# yard-ice-fpga.net
KiCad netlist of a schematic drawn in Altium Designer
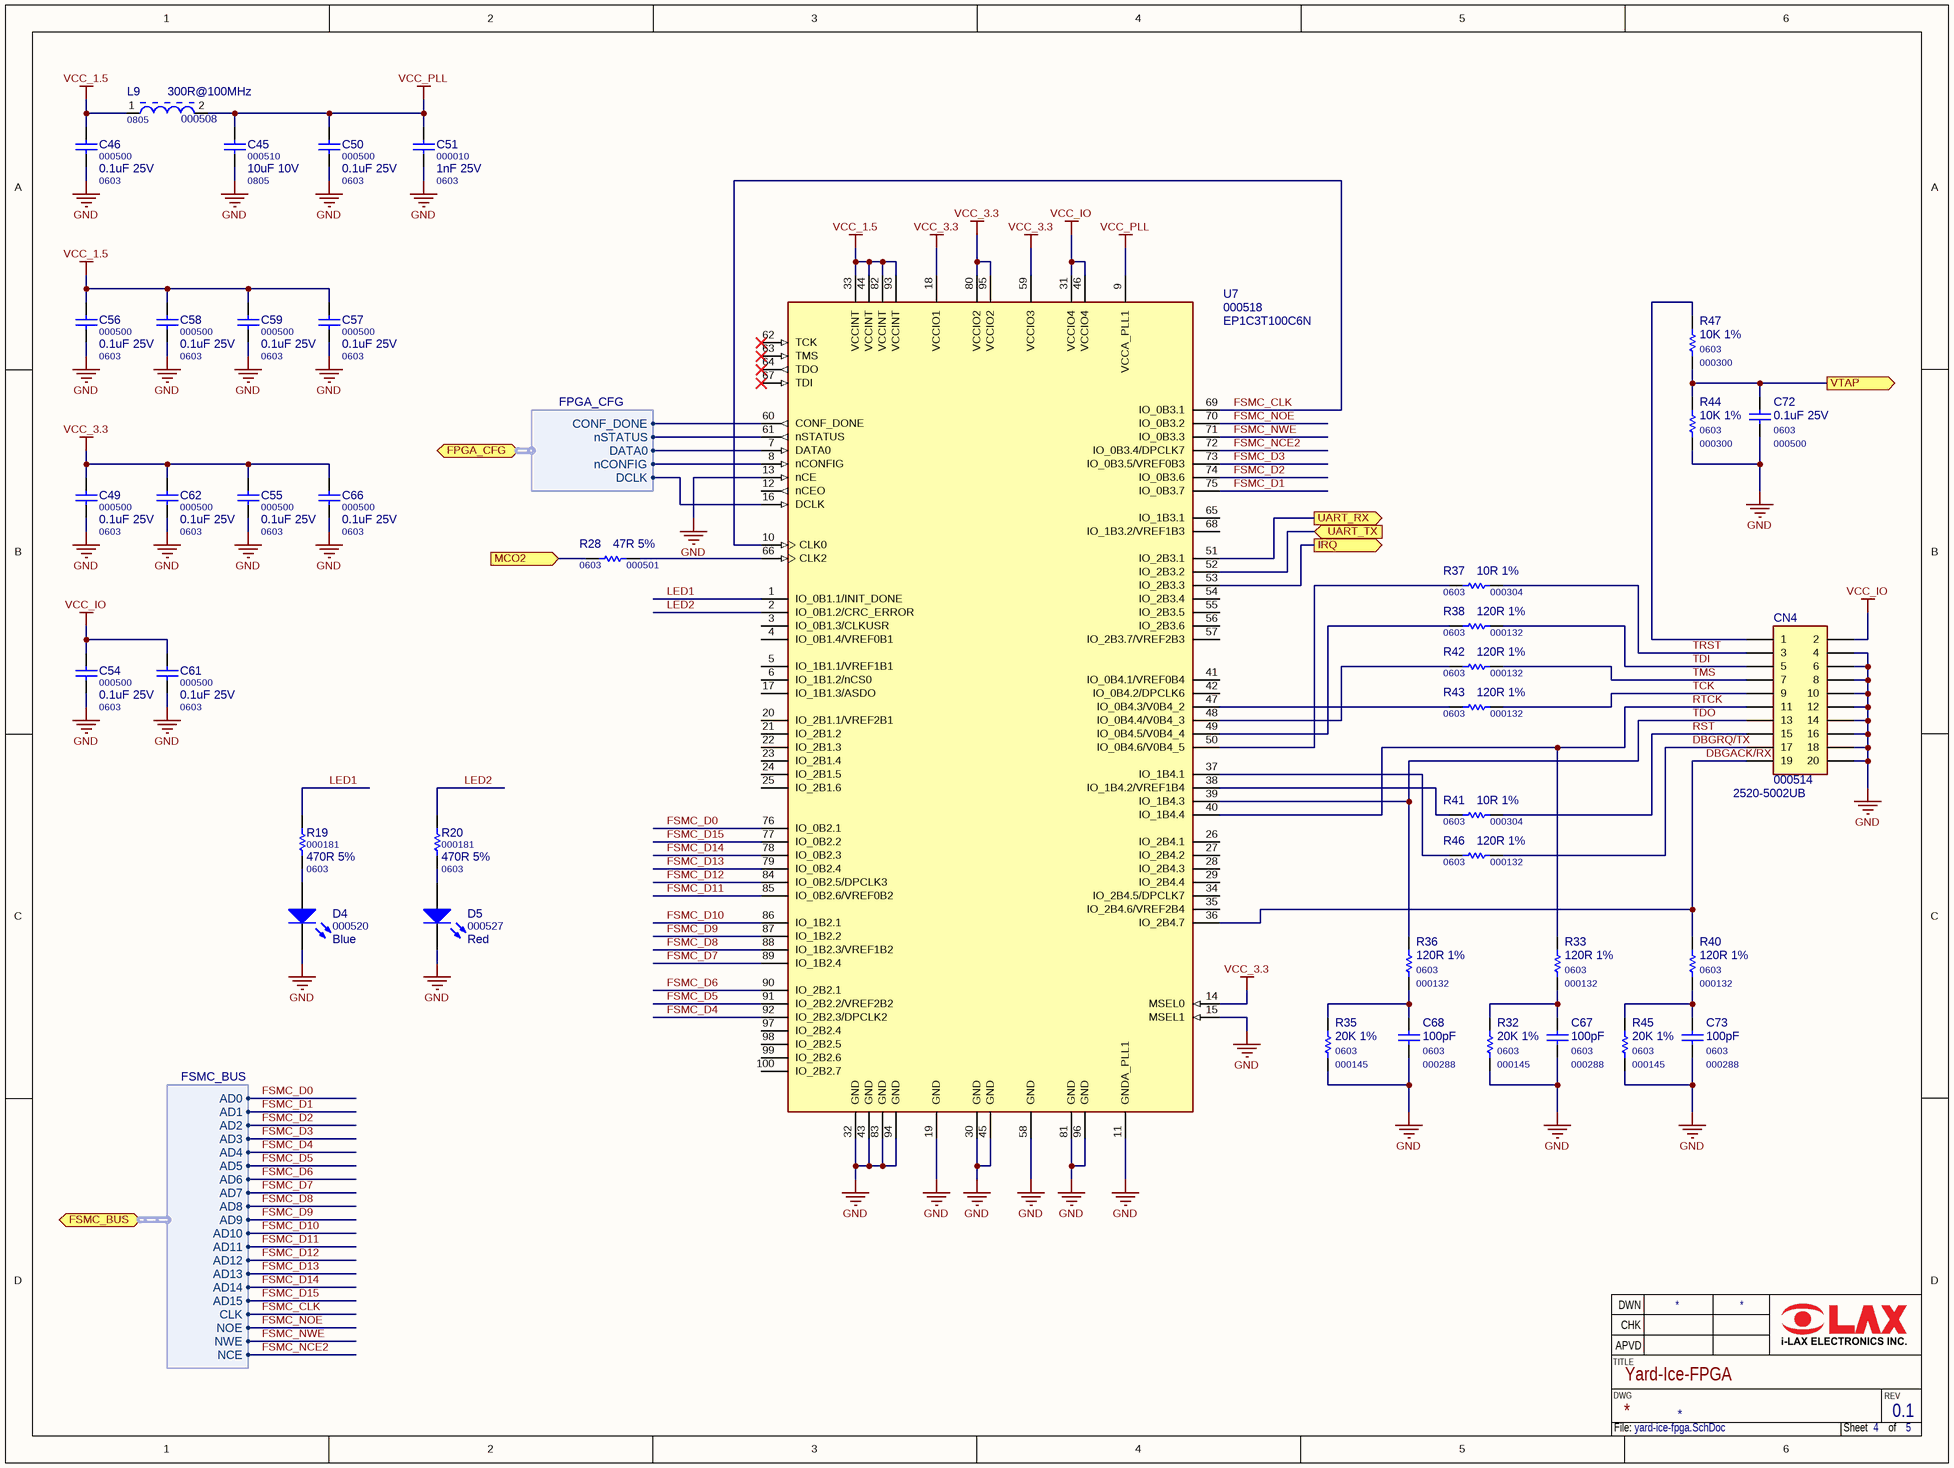
[diagram p0: yard-ice-fpga.SchDoc]

(export (version "E")
  (design (tool "Eeschema 10.0.6"))
  (components
    (comp (ref "C45")
      (value "000510")
      (footprint "C0805M")
      (description "SMD Ceramic Chip Capacitor - 0805 - X7R")
      (fields
        (field (name "ALTIUM_VALUE") "10uF 10V")
        (field (name "PACKAGE") "0805")
        (field (name "MF") "TDK")
      )
      (libsource (lib "discrete-sm") (part "C0805"))
    )
    (comp (ref "C46")
      (value "000500")
      (footprint "C0603M")
      (description "SMD Ceramic Chip Capacitor - 0603 - X7R")
      (fields
        (field (name "ALTIUM_VALUE") "0.1uF 25V")
        (field (name "PACKAGE") "0603")
        (field (name "MF") "TDK")
      )
      (libsource (lib "discrete-sm") (part "C0603"))
    )
    (comp (ref "C49")
      (value "000500")
      (footprint "C0603M")
      (description "SMD Ceramic Chip Capacitor - 0603 - X7R")
      (fields
        (field (name "ALTIUM_VALUE") "0.1uF 25V")
        (field (name "PACKAGE") "0603")
        (field (name "MF") "TDK")
      )
      (libsource (lib "discrete-sm") (part "C0603"))
    )
    (comp (ref "C50")
      (value "000500")
      (footprint "C0603M")
      (description "SMD Ceramic Chip Capacitor - 0603 - X7R")
      (fields
        (field (name "ALTIUM_VALUE") "0.1uF 25V")
        (field (name "PACKAGE") "0603")
        (field (name "MF") "TDK")
      )
      (libsource (lib "discrete-sm") (part "C0603"))
    )
    (comp (ref "C51")
      (value "000010")
      (footprint "C0603M")
      (description "SMD Ceramic Chip Capacitor - 0603 - X7R")
      (fields (field (name "ALTIUM_VALUE") "1nF 25V") (field (name "PACKAGE") "0603"))
      (libsource (lib "discrete-sm") (part "C0603"))
    )
    (comp (ref "C54")
      (value "000500")
      (footprint "C0603M")
      (description "SMD Ceramic Chip Capacitor - 0603 - X7R")
      (fields
        (field (name "ALTIUM_VALUE") "0.1uF 25V")
        (field (name "PACKAGE") "0603")
        (field (name "MF") "TDK")
      )
      (libsource (lib "discrete-sm") (part "C0603"))
    )
    (comp (ref "C55")
      (value "000500")
      (footprint "C0603M")
      (description "SMD Ceramic Chip Capacitor - 0603 - X7R")
      (fields
        (field (name "ALTIUM_VALUE") "0.1uF 25V")
        (field (name "PACKAGE") "0603")
        (field (name "MF") "TDK")
      )
      (libsource (lib "discrete-sm") (part "C0603"))
    )
    (comp (ref "C56")
      (value "000500")
      (footprint "C0603M")
      (description "SMD Ceramic Chip Capacitor - 0603 - X7R")
      (fields
        (field (name "ALTIUM_VALUE") "0.1uF 25V")
        (field (name "PACKAGE") "0603")
        (field (name "MF") "TDK")
      )
      (libsource (lib "discrete-sm") (part "C0603"))
    )
    (comp (ref "C57")
      (value "000500")
      (footprint "C0603M")
      (description "SMD Ceramic Chip Capacitor - 0603 - X7R")
      (fields
        (field (name "ALTIUM_VALUE") "0.1uF 25V")
        (field (name "PACKAGE") "0603")
        (field (name "MF") "TDK")
      )
      (libsource (lib "discrete-sm") (part "C0603"))
    )
    (comp (ref "C58")
      (value "000500")
      (footprint "C0603M")
      (description "SMD Ceramic Chip Capacitor - 0603 - X7R")
      (fields
        (field (name "ALTIUM_VALUE") "0.1uF 25V")
        (field (name "PACKAGE") "0603")
        (field (name "MF") "TDK")
      )
      (libsource (lib "discrete-sm") (part "C0603"))
    )
    (comp (ref "C59")
      (value "000500")
      (footprint "C0603M")
      (description "SMD Ceramic Chip Capacitor - 0603 - X7R")
      (fields
        (field (name "ALTIUM_VALUE") "0.1uF 25V")
        (field (name "PACKAGE") "0603")
        (field (name "MF") "TDK")
      )
      (libsource (lib "discrete-sm") (part "C0603"))
    )
    (comp (ref "C61")
      (value "000500")
      (footprint "C0603M")
      (description "SMD Ceramic Chip Capacitor - 0603 - X7R")
      (fields
        (field (name "ALTIUM_VALUE") "0.1uF 25V")
        (field (name "PACKAGE") "0603")
        (field (name "MF") "TDK")
      )
      (libsource (lib "discrete-sm") (part "C0603"))
    )
    (comp (ref "C62")
      (value "000500")
      (footprint "C0603M")
      (description "SMD Ceramic Chip Capacitor - 0603 - X7R")
      (fields
        (field (name "ALTIUM_VALUE") "0.1uF 25V")
        (field (name "PACKAGE") "0603")
        (field (name "MF") "TDK")
      )
      (libsource (lib "discrete-sm") (part "C0603"))
    )
    (comp (ref "C66")
      (value "000500")
      (footprint "C0603M")
      (description "SMD Ceramic Chip Capacitor - 0603 - X7R")
      (fields
        (field (name "ALTIUM_VALUE") "0.1uF 25V")
        (field (name "PACKAGE") "0603")
        (field (name "MF") "TDK")
      )
      (libsource (lib "discrete-sm") (part "C0603"))
    )
    (comp (ref "C67")
      (value "000288")
      (footprint "C0603M")
      (description "SMD Ceramic Chip Capacitor - 0603")
      (fields (field (name "ALTIUM_VALUE") "100pF") (field (name "PACKAGE") "0603"))
      (libsource (lib "discrete-sm") (part "C0603"))
    )
    (comp (ref "C68")
      (value "000288")
      (footprint "C0603M")
      (description "SMD Ceramic Chip Capacitor - 0603")
      (fields (field (name "ALTIUM_VALUE") "100pF") (field (name "PACKAGE") "0603"))
      (libsource (lib "discrete-sm") (part "C0603"))
    )
    (comp (ref "C72")
      (value "000500")
      (footprint "C0603M")
      (description "SMD Ceramic Chip Capacitor - 0603 - X7R")
      (fields
        (field (name "ALTIUM_VALUE") "0.1uF 25V")
        (field (name "PACKAGE") "0603")
        (field (name "MF") "TDK")
      )
      (libsource (lib "discrete-sm") (part "C0603"))
    )
    (comp (ref "C73")
      (value "000288")
      (footprint "C0603M")
      (description "SMD Ceramic Chip Capacitor - 0603")
      (fields (field (name "ALTIUM_VALUE") "100pF") (field (name "PACKAGE") "0603"))
      (libsource (lib "discrete-sm") (part "C0603"))
    )
    (comp (ref "CN4")
      (value "000514")
      (footprint "TST-110-04-G-D-RA")
      (description "Shrouded Header, 20 Pos, Right Angle")
      (fields (field (name "ALTIUM_VALUE") "2520-5002UB") (field (name "MF") "3M"))
      (libsource (lib "samtec-board-to-board") (part "Header 10X2"))
    )
    (comp (ref "D4")
      (value "000520")
      (footprint "LED0805L LP")
      (description "LED SMD 0805")
      (fields (field (name "ALTIUM_VALUE") "Blue"))
      (libsource (lib "discrete-sm") (part "LED0805LP"))
    )
    (comp (ref "D5")
      (value "000527")
      (footprint "LED0805L LP")
      (description "LED SMD 0805")
      (fields (field (name "ALTIUM_VALUE") "Red"))
      (libsource (lib "discrete-sm") (part "LED0805LP"))
    )
    (comp (ref "L9")
      (value "000508")
      (footprint "L0805M")
      (description "SMD Ferrite Bead 0805")
      (fields
        (field (name "ALTIUM_VALUE") "300R@100MHz")
        (field (name "PACKAGE") "0805")
        (field (name "MF") "TDK")
      )
      (libsource (lib "discrete-sm") (part "L0805"))
    )
    (comp (ref "R19")
      (value "000181")
      (footprint "R0603M")
      (description "SMD Chip Resistor - 0603")
      (fields (field (name "ALTIUM_VALUE") "470R 5%") (field (name "PACKAGE") "0603"))
      (libsource (lib "discrete-sm") (part "R0603"))
    )
    (comp (ref "R20")
      (value "000181")
      (footprint "R0603M")
      (description "SMD Chip Resistor - 0603")
      (fields (field (name "ALTIUM_VALUE") "470R 5%") (field (name "PACKAGE") "0603"))
      (libsource (lib "discrete-sm") (part "R0603"))
    )
    (comp (ref "R28")
      (value "000501")
      (footprint "R0603M")
      (description "SMD Chip Resistor - 0603")
      (fields (field (name "ALTIUM_VALUE") "47R 5%") (field (name "PACKAGE") "0603"))
      (libsource (lib "discrete-sm") (part "R0603"))
    )
    (comp (ref "R32")
      (value "000145")
      (footprint "R0603M")
      (description "SMD Chip Resistor - 0603")
      (fields (field (name "ALTIUM_VALUE") "20K 1%") (field (name "PACKAGE") "0603"))
      (libsource (lib "discrete-sm") (part "R0603"))
    )
    (comp (ref "R33")
      (value "000132")
      (footprint "R0603M")
      (description "SMD Chip Resistor - 0603")
      (fields (field (name "ALTIUM_VALUE") "120R 1%") (field (name "PACKAGE") "0603"))
      (libsource (lib "discrete-sm") (part "R0603"))
    )
    (comp (ref "R35")
      (value "000145")
      (footprint "R0603M")
      (description "SMD Chip Resistor - 0603")
      (fields (field (name "ALTIUM_VALUE") "20K 1%") (field (name "PACKAGE") "0603"))
      (libsource (lib "discrete-sm") (part "R0603"))
    )
    (comp (ref "R36")
      (value "000132")
      (footprint "R0603M")
      (description "SMD Chip Resistor - 0603")
      (fields (field (name "ALTIUM_VALUE") "120R 1%") (field (name "PACKAGE") "0603"))
      (libsource (lib "discrete-sm") (part "R0603"))
    )
    (comp (ref "R37")
      (value "000304")
      (footprint "R0603M")
      (description "SMD Chip Resistor - 0603")
      (fields (field (name "ALTIUM_VALUE") "10R 1%") (field (name "PACKAGE") "0603"))
      (libsource (lib "discrete-sm") (part "R0603"))
    )
    (comp (ref "R38")
      (value "000132")
      (footprint "R0603M")
      (description "SMD Chip Resistor - 0603")
      (fields (field (name "ALTIUM_VALUE") "120R 1%") (field (name "PACKAGE") "0603"))
      (libsource (lib "discrete-sm") (part "R0603"))
    )
    (comp (ref "R40")
      (value "000132")
      (footprint "R0603M")
      (description "SMD Chip Resistor - 0603")
      (fields (field (name "ALTIUM_VALUE") "120R 1%") (field (name "PACKAGE") "0603"))
      (libsource (lib "discrete-sm") (part "R0603"))
    )
    (comp (ref "R41")
      (value "000304")
      (footprint "R0603M")
      (description "SMD Chip Resistor - 0603")
      (fields (field (name "ALTIUM_VALUE") "10R 1%") (field (name "PACKAGE") "0603"))
      (libsource (lib "discrete-sm") (part "R0603"))
    )
    (comp (ref "R42")
      (value "000132")
      (footprint "R0603M")
      (description "SMD Chip Resistor - 0603")
      (fields (field (name "ALTIUM_VALUE") "120R 1%") (field (name "PACKAGE") "0603"))
      (libsource (lib "discrete-sm") (part "R0603"))
    )
    (comp (ref "R43")
      (value "000132")
      (footprint "R0603M")
      (description "SMD Chip Resistor - 0603")
      (fields (field (name "ALTIUM_VALUE") "120R 1%") (field (name "PACKAGE") "0603"))
      (libsource (lib "discrete-sm") (part "R0603"))
    )
    (comp (ref "R44")
      (value "000300")
      (footprint "R0603M")
      (description "SMD Chip Resistor - 0603")
      (fields (field (name "ALTIUM_VALUE") "10K 1%") (field (name "PACKAGE") "0603"))
      (libsource (lib "discrete-sm") (part "R0603"))
    )
    (comp (ref "R45")
      (value "000145")
      (footprint "R0603M")
      (description "SMD Chip Resistor - 0603")
      (fields (field (name "ALTIUM_VALUE") "20K 1%") (field (name "PACKAGE") "0603"))
      (libsource (lib "discrete-sm") (part "R0603"))
    )
    (comp (ref "R46")
      (value "000132")
      (footprint "R0603M")
      (description "SMD Chip Resistor - 0603")
      (fields (field (name "ALTIUM_VALUE") "120R 1%") (field (name "PACKAGE") "0603"))
      (libsource (lib "discrete-sm") (part "R0603"))
    )
    (comp (ref "R47")
      (value "000300")
      (footprint "R0603M")
      (description "SMD Chip Resistor - 0603")
      (fields (field (name "ALTIUM_VALUE") "10K 1%") (field (name "PACKAGE") "0603"))
      (libsource (lib "discrete-sm") (part "R0603"))
    )
    (comp (ref "U7")
      (value "000518")
      (footprint "TQFP-100")
      (description "Cyclone FPGA")
      (fields (field (name "ALTIUM_VALUE") "EP1C3T100C6N") (field (name "MF") "Altera"))
      (libsource (lib "altera-cyclone") (part "EP1C3T100C8N"))
    )
  )
  (nets
    (net (code "3") (name "/CONF_DONE") (class "Default")
      (node (ref "U7") (pin "60") (pinfunction "CONF_DONE_60") (pintype "output"))
    )
    (net (code "4") (name "/DATA0") (class "Default")
      (node (ref "U7") (pin "7") (pinfunction "DATA0_7") (pintype "input"))
    )
    (net (code "5") (name "/DBGACK{slash}RX") (class "Default")
      (node (ref "CN4") (pin "19") (pinfunction "19_19") (pintype "passive"))
      (node (ref "R40") (pin "1") (pinfunction "1_1") (pintype "passive"))
      (node (ref "U7") (pin "36") (pinfunction "IO_2B4.7_36") (pintype "tri_state"))
    )
    (net (code "6") (name "/DBGRQ{slash}TX") (class "Default")
      (node (ref "CN4") (pin "17") (pinfunction "17_17") (pintype "passive"))
      (node (ref "R46") (pin "1") (pinfunction "1_1") (pintype "passive"))
    )
    (net (code "7") (name "/DCLK") (class "Default")
      (node (ref "U7") (pin "16") (pinfunction "DCLK_16") (pintype "input"))
    )
    (net (code "8") (name "/FSMC_CLK") (class "Default")
      (node (ref "U7") (pin "10") (pinfunction "CLK0_10") (pintype "input"))
      (node (ref "U7") (pin "69") (pinfunction "IO_0B3.1_69") (pintype "tri_state"))
    )
    (net (code "9") (name "/FSMC_D0") (class "Default")
      (node (ref "U7") (pin "76") (pinfunction "IO_0B2.1_76") (pintype "tri_state"))
    )
    (net (code "10") (name "/FSMC_D1") (class "Default")
      (node (ref "U7") (pin "75") (pinfunction "IO_0B3.7_75") (pintype "tri_state"))
    )
    (net (code "11") (name "/FSMC_D2") (class "Default")
      (node (ref "U7") (pin "74") (pinfunction "IO_0B3.6_74") (pintype "tri_state"))
    )
    (net (code "12") (name "/FSMC_D3") (class "Default")
      (node (ref "U7") (pin "73") (pinfunction "IO_0B3.5/VREF0B3_73") (pintype "tri_state"))
    )
    (net (code "13") (name "/FSMC_D4") (class "Default")
      (node (ref "U7") (pin "92") (pinfunction "IO_2B2.3/DPCLK2_92") (pintype "tri_state"))
    )
    (net (code "14") (name "/FSMC_D5") (class "Default")
      (node (ref "U7") (pin "91") (pinfunction "IO_2B2.2/VREF2B2_91") (pintype "tri_state"))
    )
    (net (code "15") (name "/FSMC_D6") (class "Default")
      (node (ref "U7") (pin "90") (pinfunction "IO_2B2.1_90") (pintype "tri_state"))
    )
    (net (code "16") (name "/FSMC_D7") (class "Default")
      (node (ref "U7") (pin "89") (pinfunction "IO_1B2.4_89") (pintype "tri_state"))
    )
    (net (code "17") (name "/FSMC_D8") (class "Default")
      (node (ref "U7") (pin "88") (pinfunction "IO_1B2.3/VREF1B2_88") (pintype "tri_state"))
    )
    (net (code "18") (name "/FSMC_D9") (class "Default")
      (node (ref "U7") (pin "87") (pinfunction "IO_1B2.2_87") (pintype "tri_state"))
    )
    (net (code "19") (name "/FSMC_D10") (class "Default")
      (node (ref "U7") (pin "86") (pinfunction "IO_1B2.1_86") (pintype "tri_state"))
    )
    (net (code "20") (name "/FSMC_D11") (class "Default")
      (node (ref "U7") (pin "85") (pinfunction "IO_0B2.6/VREF0B2_85") (pintype "tri_state"))
    )
    (net (code "21") (name "/FSMC_D12") (class "Default")
      (node (ref "U7") (pin "84") (pinfunction "IO_0B2.5/DPCLK3_84") (pintype "tri_state"))
    )
    (net (code "22") (name "/FSMC_D13") (class "Default")
      (node (ref "U7") (pin "79") (pinfunction "IO_0B2.4_79") (pintype "tri_state"))
    )
    (net (code "23") (name "/FSMC_D14") (class "Default")
      (node (ref "U7") (pin "78") (pinfunction "IO_0B2.3_78") (pintype "tri_state"))
    )
    (net (code "24") (name "/FSMC_D15") (class "Default")
      (node (ref "U7") (pin "77") (pinfunction "IO_0B2.2_77") (pintype "tri_state"))
    )
    (net (code "25") (name "/FSMC_NCE2") (class "Default")
      (node (ref "U7") (pin "72") (pinfunction "IO_0B3.4/DPCLK7_72") (pintype "tri_state"))
    )
    (net (code "26") (name "/FSMC_NOE") (class "Default")
      (node (ref "U7") (pin "70") (pinfunction "IO_0B3.2_70") (pintype "tri_state"))
    )
    (net (code "27") (name "/FSMC_NWE") (class "Default")
      (node (ref "U7") (pin "71") (pinfunction "IO_0B3.3_71") (pintype "tri_state"))
    )
    (net (code "28") (name "/IRQ") (class "Default")
      (node (ref "U7") (pin "53") (pinfunction "IO_2B3.3_53") (pintype "tri_state"))
    )
    (net (code "29") (name "/LED1") (class "Default")
      (node (ref "R19") (pin "1") (pinfunction "1_1") (pintype "passive"))
      (node (ref "U7") (pin "1") (pinfunction "IO_0B1.1/INIT_DONE_1") (pintype "tri_state"))
    )
    (net (code "30") (name "/LED2") (class "Default")
      (node (ref "R20") (pin "1") (pinfunction "1_1") (pintype "passive"))
      (node (ref "U7") (pin "2") (pinfunction "IO_0B1.2/CRC_ERROR_2") (pintype "tri_state"))
    )
    (net (code "31") (name "/MCO2") (class "Default")
      (node (ref "R28") (pin "2") (pinfunction "2_2") (pintype "passive"))
    )
    (net (code "32") (name "/RST") (class "Default")
      (node (ref "CN4") (pin "15") (pinfunction "15_15") (pintype "passive"))
      (node (ref "R41") (pin "1") (pinfunction "1_1") (pintype "passive"))
    )
    (net (code "33") (name "/RTCK") (class "Default")
      (node (ref "CN4") (pin "11") (pinfunction "11_11") (pintype "passive"))
      (node (ref "R33") (pin "1") (pinfunction "1_1") (pintype "passive"))
      (node (ref "U7") (pin "40") (pinfunction "IO_1B4.4_40") (pintype "tri_state"))
    )
    (net (code "34") (name "/TCK") (class "Default")
      (node (ref "CN4") (pin "9") (pinfunction "9_9") (pintype "passive"))
      (node (ref "R43") (pin "1") (pinfunction "1_1") (pintype "passive"))
    )
    (net (code "35") (name "/TDI") (class "Default")
      (node (ref "CN4") (pin "5") (pinfunction "5_5") (pintype "passive"))
      (node (ref "R38") (pin "1") (pinfunction "1_1") (pintype "passive"))
    )
    (net (code "36") (name "/TDO") (class "Default")
      (node (ref "CN4") (pin "13") (pinfunction "13_13") (pintype "passive"))
      (node (ref "R36") (pin "1") (pinfunction "1_1") (pintype "passive"))
      (node (ref "U7") (pin "39") (pinfunction "IO_1B4.3_39") (pintype "tri_state"))
    )
    (net (code "37") (name "/TMS") (class "Default")
      (node (ref "CN4") (pin "7") (pinfunction "7_7") (pintype "passive"))
      (node (ref "R42") (pin "1") (pinfunction "1_1") (pintype "passive"))
    )
    (net (code "38") (name "/TRST") (class "Default")
      (node (ref "CN4") (pin "3") (pinfunction "3_3") (pintype "passive"))
      (node (ref "R37") (pin "1") (pinfunction "1_1") (pintype "passive"))
    )
    (net (code "39") (name "/UART_RX") (class "Default")
      (node (ref "U7") (pin "51") (pinfunction "IO_2B3.1_51") (pintype "tri_state"))
    )
    (net (code "40") (name "/UART_TX") (class "Default")
      (node (ref "U7") (pin "52") (pinfunction "IO_2B3.2_52") (pintype "tri_state"))
    )
    (net (code "41") (name "/VTAP") (class "Default")
      (node (ref "C72") (pin "1") (pinfunction "1_1") (pintype "passive"))
      (node (ref "R44") (pin "1") (pinfunction "1_1") (pintype "passive"))
      (node (ref "R47") (pin "2") (pinfunction "2_2") (pintype "passive"))
    )
    (net (code "42") (name "/nCONFIG") (class "Default")
      (node (ref "U7") (pin "8") (pinfunction "nCONFIG_8") (pintype "input"))
    )
    (net (code "43") (name "/nSTATUS") (class "Default")
      (node (ref "U7") (pin "61") (pinfunction "nSTATUS_61") (pintype "output"))
    )
    (net (code "46") (name "GND") (class "Default")
      (node (ref "C45") (pin "2") (pinfunction "2_2") (pintype "passive"))
      (node (ref "C46") (pin "2") (pinfunction "2_2") (pintype "passive"))
      (node (ref "C49") (pin "2") (pinfunction "2_2") (pintype "passive"))
      (node (ref "C50") (pin "2") (pinfunction "2_2") (pintype "passive"))
      (node (ref "C51") (pin "2") (pinfunction "2_2") (pintype "passive"))
      (node (ref "C54") (pin "2") (pinfunction "2_2") (pintype "passive"))
      (node (ref "C55") (pin "2") (pinfunction "2_2") (pintype "passive"))
      (node (ref "C56") (pin "2") (pinfunction "2_2") (pintype "passive"))
      (node (ref "C57") (pin "2") (pinfunction "2_2") (pintype "passive"))
      (node (ref "C58") (pin "2") (pinfunction "2_2") (pintype "passive"))
      (node (ref "C59") (pin "2") (pinfunction "2_2") (pintype "passive"))
      (node (ref "C61") (pin "2") (pinfunction "2_2") (pintype "passive"))
      (node (ref "C62") (pin "2") (pinfunction "2_2") (pintype "passive"))
      (node (ref "C66") (pin "2") (pinfunction "2_2") (pintype "passive"))
      (node (ref "C67") (pin "2") (pinfunction "2_2") (pintype "passive"))
      (node (ref "C68") (pin "2") (pinfunction "2_2") (pintype "passive"))
      (node (ref "C72") (pin "2") (pinfunction "2_2") (pintype "passive"))
      (node (ref "C73") (pin "2") (pinfunction "2_2") (pintype "passive"))
      (node (ref "CN4") (pin "10") (pinfunction "10_10") (pintype "passive"))
      (node (ref "CN4") (pin "12") (pinfunction "12_12") (pintype "passive"))
      (node (ref "CN4") (pin "14") (pinfunction "14_14") (pintype "passive"))
      (node (ref "CN4") (pin "16") (pinfunction "16_16") (pintype "passive"))
      (node (ref "CN4") (pin "18") (pinfunction "18_18") (pintype "passive"))
      (node (ref "CN4") (pin "20") (pinfunction "20_20") (pintype "passive"))
      (node (ref "CN4") (pin "4") (pinfunction "4_4") (pintype "passive"))
      (node (ref "CN4") (pin "6") (pinfunction "6_6") (pintype "passive"))
      (node (ref "CN4") (pin "8") (pinfunction "8_8") (pintype "passive"))
      (node (ref "D4") (pin "2") (pinfunction "K_2") (pintype "passive"))
      (node (ref "D5") (pin "2") (pinfunction "K_2") (pintype "passive"))
      (node (ref "R32") (pin "2") (pinfunction "2_2") (pintype "passive"))
      (node (ref "R35") (pin "2") (pinfunction "2_2") (pintype "passive"))
      (node (ref "R44") (pin "2") (pinfunction "2_2") (pintype "passive"))
      (node (ref "R45") (pin "2") (pinfunction "2_2") (pintype "passive"))
      (node (ref "U7") (pin "11") (pinfunction "GNDA_PLL1_11") (pintype "power_in"))
      (node (ref "U7") (pin "13") (pinfunction "nCE_13") (pintype "input"))
      (node (ref "U7") (pin "15") (pinfunction "MSEL1_15") (pintype "input"))
      (node (ref "U7") (pin "19") (pinfunction "GND_19") (pintype "power_in"))
      (node (ref "U7") (pin "30") (pinfunction "GND_30") (pintype "power_in"))
      (node (ref "U7") (pin "32") (pinfunction "GND_32") (pintype "power_in"))
      (node (ref "U7") (pin "43") (pinfunction "GND_43") (pintype "power_in"))
      (node (ref "U7") (pin "45") (pinfunction "GND_45") (pintype "power_in"))
      (node (ref "U7") (pin "58") (pinfunction "GND_58") (pintype "power_in"))
      (node (ref "U7") (pin "81") (pinfunction "GND_81") (pintype "power_in"))
      (node (ref "U7") (pin "83") (pinfunction "GND_83") (pintype "power_in"))
      (node (ref "U7") (pin "94") (pinfunction "GND_94") (pintype "power_in"))
      (node (ref "U7") (pin "96") (pinfunction "GND_96") (pintype "power_in"))
    )
    (net (code "47") (name "Net-(C67-Pad1)") (class "Default")
      (node (ref "C67") (pin "1") (pinfunction "1_1") (pintype "passive"))
      (node (ref "R32") (pin "1") (pinfunction "1_1") (pintype "passive"))
      (node (ref "R33") (pin "2") (pinfunction "2_2") (pintype "passive"))
    )
    (net (code "48") (name "Net-(C68-Pad1)") (class "Default")
      (node (ref "C68") (pin "1") (pinfunction "1_1") (pintype "passive"))
      (node (ref "R35") (pin "1") (pinfunction "1_1") (pintype "passive"))
      (node (ref "R36") (pin "2") (pinfunction "2_2") (pintype "passive"))
    )
    (net (code "49") (name "Net-(C73-Pad1)") (class "Default")
      (node (ref "C73") (pin "1") (pinfunction "1_1") (pintype "passive"))
      (node (ref "R40") (pin "2") (pinfunction "2_2") (pintype "passive"))
      (node (ref "R45") (pin "1") (pinfunction "1_1") (pintype "passive"))
    )
    (net (code "50") (name "Net-(CN4-Pad1)") (class "Default")
      (node (ref "CN4") (pin "1") (pinfunction "1_1") (pintype "passive"))
      (node (ref "R47") (pin "1") (pinfunction "1_1") (pintype "passive"))
    )
    (net (code "51") (name "Net-(D4-A)") (class "Default")
      (node (ref "D4") (pin "1") (pinfunction "A_1") (pintype "passive"))
      (node (ref "R19") (pin "2") (pinfunction "2_2") (pintype "passive"))
    )
    (net (code "52") (name "Net-(D5-A)") (class "Default")
      (node (ref "D5") (pin "1") (pinfunction "A_1") (pintype "passive"))
      (node (ref "R20") (pin "2") (pinfunction "2_2") (pintype "passive"))
    )
    (net (code "53") (name "Net-(U7-CLK2)") (class "Default")
      (node (ref "R28") (pin "1") (pinfunction "1_1") (pintype "passive"))
      (node (ref "U7") (pin "66") (pinfunction "CLK2_66") (pintype "input"))
    )
    (net (code "54") (name "Net-(U7-IO_0B4.3{slash}V0B4_2)") (class "Default")
      (node (ref "R43") (pin "2") (pinfunction "2_2") (pintype "passive"))
      (node (ref "U7") (pin "47") (pinfunction "IO_0B4.3/V0B4_2_47") (pintype "tri_state"))
    )
    (net (code "55") (name "Net-(U7-IO_0B4.4{slash}V0B4_3)") (class "Default")
      (node (ref "R42") (pin "2") (pinfunction "2_2") (pintype "passive"))
      (node (ref "U7") (pin "48") (pinfunction "IO_0B4.4/V0B4_3_48") (pintype "tri_state"))
    )
    (net (code "56") (name "Net-(U7-IO_0B4.5{slash}V0B4_4)") (class "Default")
      (node (ref "R38") (pin "2") (pinfunction "2_2") (pintype "passive"))
      (node (ref "U7") (pin "49") (pinfunction "IO_0B4.5/V0B4_4_49") (pintype "tri_state"))
    )
    (net (code "57") (name "Net-(U7-IO_0B4.6{slash}V0B4_5)") (class "Default")
      (node (ref "R37") (pin "2") (pinfunction "2_2") (pintype "passive"))
      (node (ref "U7") (pin "50") (pinfunction "IO_0B4.6/V0B4_5_50") (pintype "tri_state"))
    )
    (net (code "58") (name "Net-(U7-IO_1B4.1)") (class "Default")
      (node (ref "R46") (pin "2") (pinfunction "2_2") (pintype "passive"))
      (node (ref "U7") (pin "37") (pinfunction "IO_1B4.1_37") (pintype "tri_state"))
    )
    (net (code "59") (name "Net-(U7-IO_1B4.2{slash}VREF1B4)") (class "Default")
      (node (ref "R41") (pin "2") (pinfunction "2_2") (pintype "passive"))
      (node (ref "U7") (pin "38") (pinfunction "IO_1B4.2/VREF1B4_38") (pintype "tri_state"))
    )
    (net (code "60") (name "VCC_1.5") (class "Default")
      (node (ref "C46") (pin "1") (pinfunction "1_1") (pintype "passive"))
      (node (ref "C56") (pin "1") (pinfunction "1_1") (pintype "passive"))
      (node (ref "C57") (pin "1") (pinfunction "1_1") (pintype "passive"))
      (node (ref "C58") (pin "1") (pinfunction "1_1") (pintype "passive"))
      (node (ref "C59") (pin "1") (pinfunction "1_1") (pintype "passive"))
      (node (ref "L9") (pin "1") (pinfunction "1_1") (pintype "passive"))
      (node (ref "U7") (pin "33") (pinfunction "VCCINT_33") (pintype "power_in"))
      (node (ref "U7") (pin "44") (pinfunction "VCCINT_44") (pintype "power_in"))
      (node (ref "U7") (pin "82") (pinfunction "VCCINT_82") (pintype "power_in"))
      (node (ref "U7") (pin "93") (pinfunction "VCCINT_93") (pintype "power_in"))
    )
    (net (code "61") (name "VCC_3.3") (class "Default")
      (node (ref "C49") (pin "1") (pinfunction "1_1") (pintype "passive"))
      (node (ref "C55") (pin "1") (pinfunction "1_1") (pintype "passive"))
      (node (ref "C62") (pin "1") (pinfunction "1_1") (pintype "passive"))
      (node (ref "C66") (pin "1") (pinfunction "1_1") (pintype "passive"))
      (node (ref "U7") (pin "14") (pinfunction "MSEL0_14") (pintype "input"))
      (node (ref "U7") (pin "18") (pinfunction "VCCIO1_18") (pintype "power_in"))
      (node (ref "U7") (pin "59") (pinfunction "VCCIO3_59") (pintype "power_in"))
      (node (ref "U7") (pin "80") (pinfunction "VCCIO2_80") (pintype "power_in"))
      (node (ref "U7") (pin "95") (pinfunction "VCCIO2_95") (pintype "power_in"))
    )
    (net (code "62") (name "VCC_IO") (class "Default")
      (node (ref "C54") (pin "1") (pinfunction "1_1") (pintype "passive"))
      (node (ref "C61") (pin "1") (pinfunction "1_1") (pintype "passive"))
      (node (ref "CN4") (pin "2") (pinfunction "2_2") (pintype "passive"))
      (node (ref "U7") (pin "31") (pinfunction "VCCIO4_31") (pintype "power_in"))
      (node (ref "U7") (pin "46") (pinfunction "VCCIO4_46") (pintype "power_in"))
    )
    (net (code "63") (name "VCC_PLL") (class "Default")
      (node (ref "C45") (pin "1") (pinfunction "1_1") (pintype "passive"))
      (node (ref "C50") (pin "1") (pinfunction "1_1") (pintype "passive"))
      (node (ref "C51") (pin "1") (pinfunction "1_1") (pintype "passive"))
      (node (ref "L9") (pin "2") (pinfunction "2_2") (pintype "passive"))
      (node (ref "U7") (pin "9") (pinfunction "VCCA_PLL1_9") (pintype "power_in"))
    )
    (net (code "64") (name "unconnected-(U7-IO_0B1.3{slash}CLKUSR-Pad3)") (class "Default")
      (node (ref "U7") (pin "3") (pinfunction "IO_0B1.3/CLKUSR_3") (pintype "tri_state"))
    )
    (net (code "65") (name "unconnected-(U7-IO_0B1.4{slash}VREF0B1-Pad4)") (class "Default")
      (node (ref "U7") (pin "4") (pinfunction "IO_0B1.4/VREF0B1_4") (pintype "tri_state"))
    )
    (net (code "66") (name "unconnected-(U7-IO_0B4.1{slash}VREF0B4-Pad41)") (class "Default")
      (node (ref "U7") (pin "41") (pinfunction "IO_0B4.1/VREF0B4_41") (pintype "tri_state"))
    )
    (net (code "67") (name "unconnected-(U7-IO_0B4.2{slash}DPCLK6-Pad42)") (class "Default")
      (node (ref "U7") (pin "42") (pinfunction "IO_0B4.2/DPCLK6_42") (pintype "tri_state"))
    )
    (net (code "68") (name "unconnected-(U7-IO_1B1.1{slash}VREF1B1-Pad5)") (class "Default")
      (node (ref "U7") (pin "5") (pinfunction "IO_1B1.1/VREF1B1_5") (pintype "tri_state"))
    )
    (net (code "69") (name "unconnected-(U7-IO_1B1.2{slash}nCS0-Pad6)") (class "Default")
      (node (ref "U7") (pin "6") (pinfunction "IO_1B1.2/nCS0_6") (pintype "tri_state"))
    )
    (net (code "70") (name "unconnected-(U7-IO_1B1.3{slash}ASDO-Pad17)") (class "Default")
      (node (ref "U7") (pin "17") (pinfunction "IO_1B1.3/ASDO_17") (pintype "tri_state"))
    )
    (net (code "71") (name "unconnected-(U7-IO_1B3.1-Pad65)") (class "Default")
      (node (ref "U7") (pin "65") (pinfunction "IO_1B3.1_65") (pintype "tri_state"))
    )
    (net (code "72") (name "unconnected-(U7-IO_1B3.2{slash}VREF1B3-Pad68)") (class "Default")
      (node (ref "U7") (pin "68") (pinfunction "IO_1B3.2/VREF1B3_68") (pintype "tri_state"))
    )
    (net (code "73") (name "unconnected-(U7-IO_2B1.1{slash}VREF2B1-Pad20)") (class "Default")
      (node (ref "U7") (pin "20") (pinfunction "IO_2B1.1/VREF2B1_20") (pintype "tri_state"))
    )
    (net (code "74") (name "unconnected-(U7-IO_2B1.2-Pad21)") (class "Default")
      (node (ref "U7") (pin "21") (pinfunction "IO_2B1.2_21") (pintype "tri_state"))
    )
    (net (code "75") (name "unconnected-(U7-IO_2B1.3-Pad22)") (class "Default")
      (node (ref "U7") (pin "22") (pinfunction "IO_2B1.3_22") (pintype "tri_state"))
    )
    (net (code "76") (name "unconnected-(U7-IO_2B1.4-Pad23)") (class "Default")
      (node (ref "U7") (pin "23") (pinfunction "IO_2B1.4_23") (pintype "tri_state"))
    )
    (net (code "77") (name "unconnected-(U7-IO_2B1.5-Pad24)") (class "Default")
      (node (ref "U7") (pin "24") (pinfunction "IO_2B1.5_24") (pintype "tri_state"))
    )
    (net (code "78") (name "unconnected-(U7-IO_2B1.6-Pad25)") (class "Default")
      (node (ref "U7") (pin "25") (pinfunction "IO_2B1.6_25") (pintype "tri_state"))
    )
    (net (code "79") (name "unconnected-(U7-IO_2B2.4-Pad97)") (class "Default")
      (node (ref "U7") (pin "97") (pinfunction "IO_2B2.4_97") (pintype "tri_state"))
    )
    (net (code "80") (name "unconnected-(U7-IO_2B2.5-Pad98)") (class "Default")
      (node (ref "U7") (pin "98") (pinfunction "IO_2B2.5_98") (pintype "tri_state"))
    )
    (net (code "81") (name "unconnected-(U7-IO_2B2.6-Pad99)") (class "Default")
      (node (ref "U7") (pin "99") (pinfunction "IO_2B2.6_99") (pintype "tri_state"))
    )
    (net (code "82") (name "unconnected-(U7-IO_2B2.7-Pad100)") (class "Default")
      (node (ref "U7") (pin "100") (pinfunction "IO_2B2.7_100") (pintype "tri_state"))
    )
    (net (code "83") (name "unconnected-(U7-IO_2B3.4-Pad54)") (class "Default")
      (node (ref "U7") (pin "54") (pinfunction "IO_2B3.4_54") (pintype "tri_state"))
    )
    (net (code "84") (name "unconnected-(U7-IO_2B3.5-Pad55)") (class "Default")
      (node (ref "U7") (pin "55") (pinfunction "IO_2B3.5_55") (pintype "tri_state"))
    )
    (net (code "85") (name "unconnected-(U7-IO_2B3.6-Pad56)") (class "Default")
      (node (ref "U7") (pin "56") (pinfunction "IO_2B3.6_56") (pintype "tri_state"))
    )
    (net (code "86") (name "unconnected-(U7-IO_2B3.7{slash}VREF2B3-Pad57)") (class "Default")
      (node (ref "U7") (pin "57") (pinfunction "IO_2B3.7/VREF2B3_57") (pintype "tri_state"))
    )
    (net (code "87") (name "unconnected-(U7-IO_2B4.1-Pad26)") (class "Default")
      (node (ref "U7") (pin "26") (pinfunction "IO_2B4.1_26") (pintype "tri_state"))
    )
    (net (code "88") (name "unconnected-(U7-IO_2B4.2-Pad27)") (class "Default")
      (node (ref "U7") (pin "27") (pinfunction "IO_2B4.2_27") (pintype "tri_state"))
    )
    (net (code "89") (name "unconnected-(U7-IO_2B4.3-Pad28)") (class "Default")
      (node (ref "U7") (pin "28") (pinfunction "IO_2B4.3_28") (pintype "tri_state"))
    )
    (net (code "90") (name "unconnected-(U7-IO_2B4.4-Pad29)") (class "Default")
      (node (ref "U7") (pin "29") (pinfunction "IO_2B4.4_29") (pintype "tri_state"))
    )
    (net (code "91") (name "unconnected-(U7-IO_2B4.5{slash}DPCLK7-Pad34)") (class "Default")
      (node (ref "U7") (pin "34") (pinfunction "IO_2B4.5/DPCLK7_34") (pintype "tri_state"))
    )
    (net (code "92") (name "unconnected-(U7-IO_2B4.6{slash}VREF2B4-Pad35)") (class "Default")
      (node (ref "U7") (pin "35") (pinfunction "IO_2B4.6/VREF2B4_35") (pintype "tri_state"))
    )
    (net (code "93") (name "unconnected-(U7-TCK-Pad62)") (class "Default")
      (node (ref "U7") (pin "62") (pinfunction "TCK_62") (pintype "input+no_connect"))
    )
    (net (code "94") (name "unconnected-(U7-TDI-Pad67)") (class "Default")
      (node (ref "U7") (pin "67") (pinfunction "TDI_67") (pintype "input+no_connect"))
    )
    (net (code "95") (name "unconnected-(U7-TDO-Pad64)") (class "Default")
      (node (ref "U7") (pin "64") (pinfunction "TDO_64") (pintype "output+no_connect"))
    )
    (net (code "96") (name "unconnected-(U7-TMS-Pad63)") (class "Default")
      (node (ref "U7") (pin "63") (pinfunction "TMS_63") (pintype "input+no_connect"))
    )
    (net (code "97") (name "unconnected-(U7-nCEO-Pad12)") (class "Default")
      (node (ref "U7") (pin "12") (pinfunction "nCEO_12") (pintype "output"))
    )
  )
)
